# cryptostick-0v1.net
KiCad netlist of a schematic drawn in EAGLE
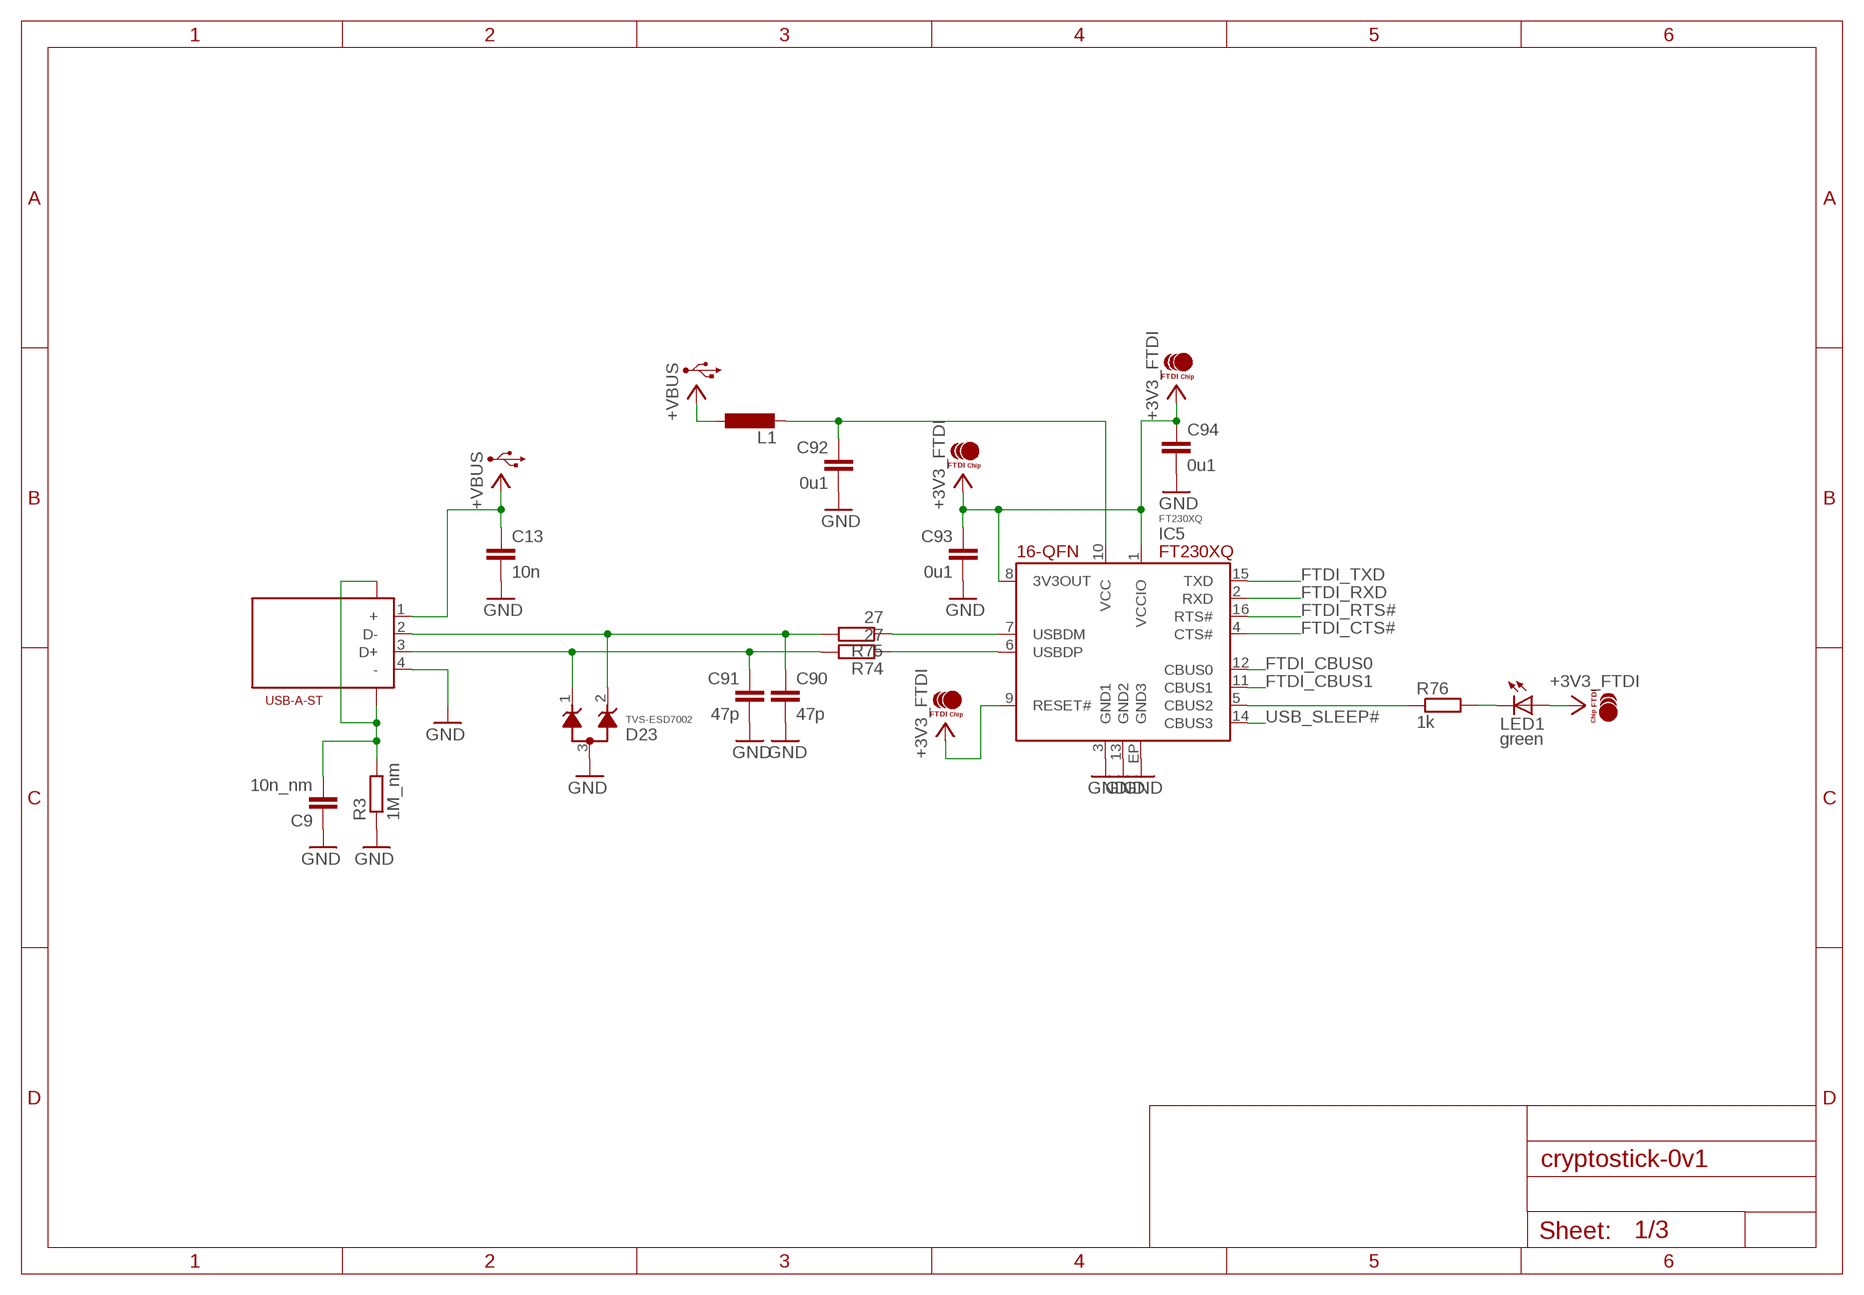
[diagram p0: schematic, sheet 1]
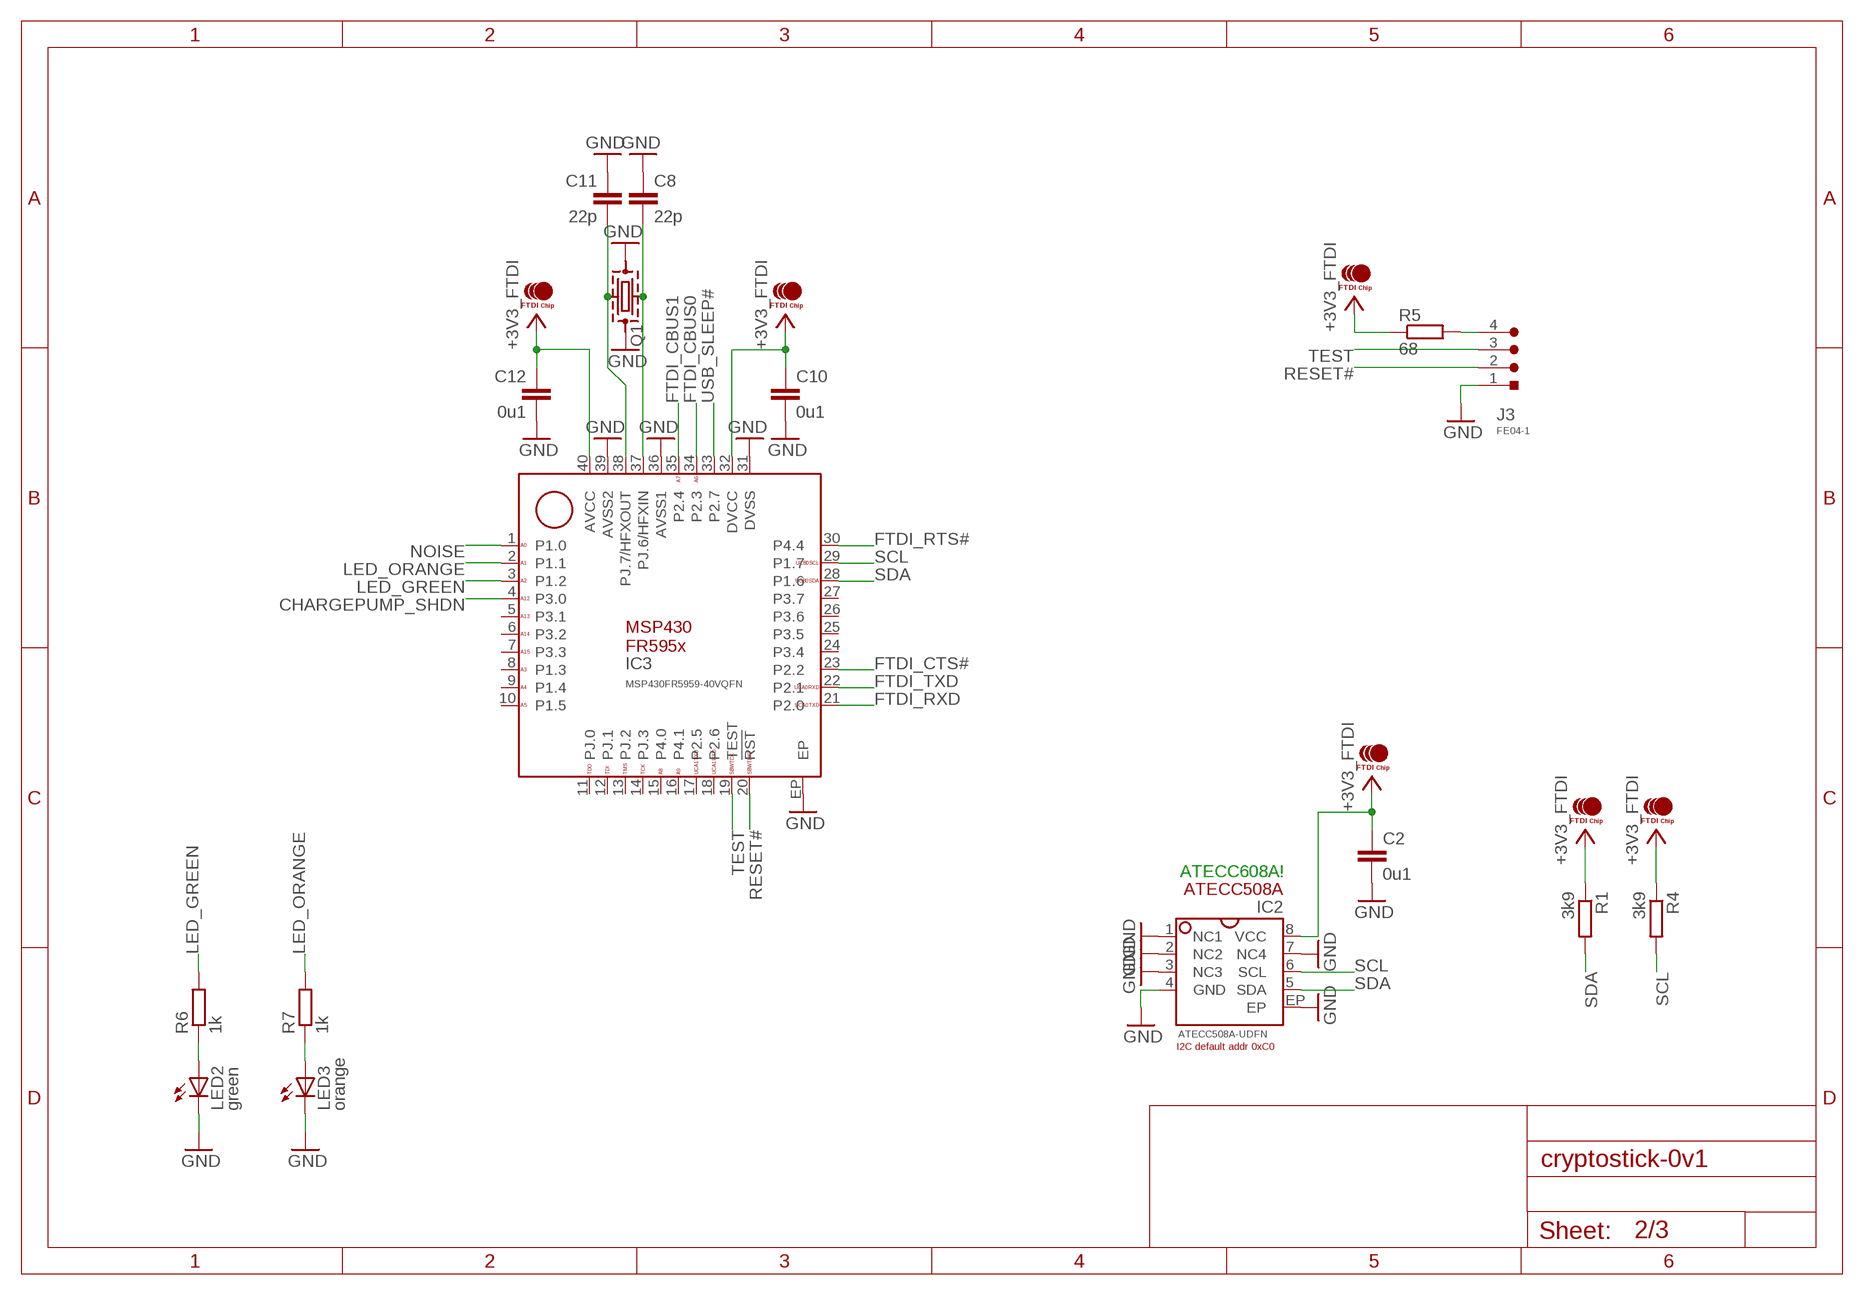
[diagram p1: schematic, sheet 2]
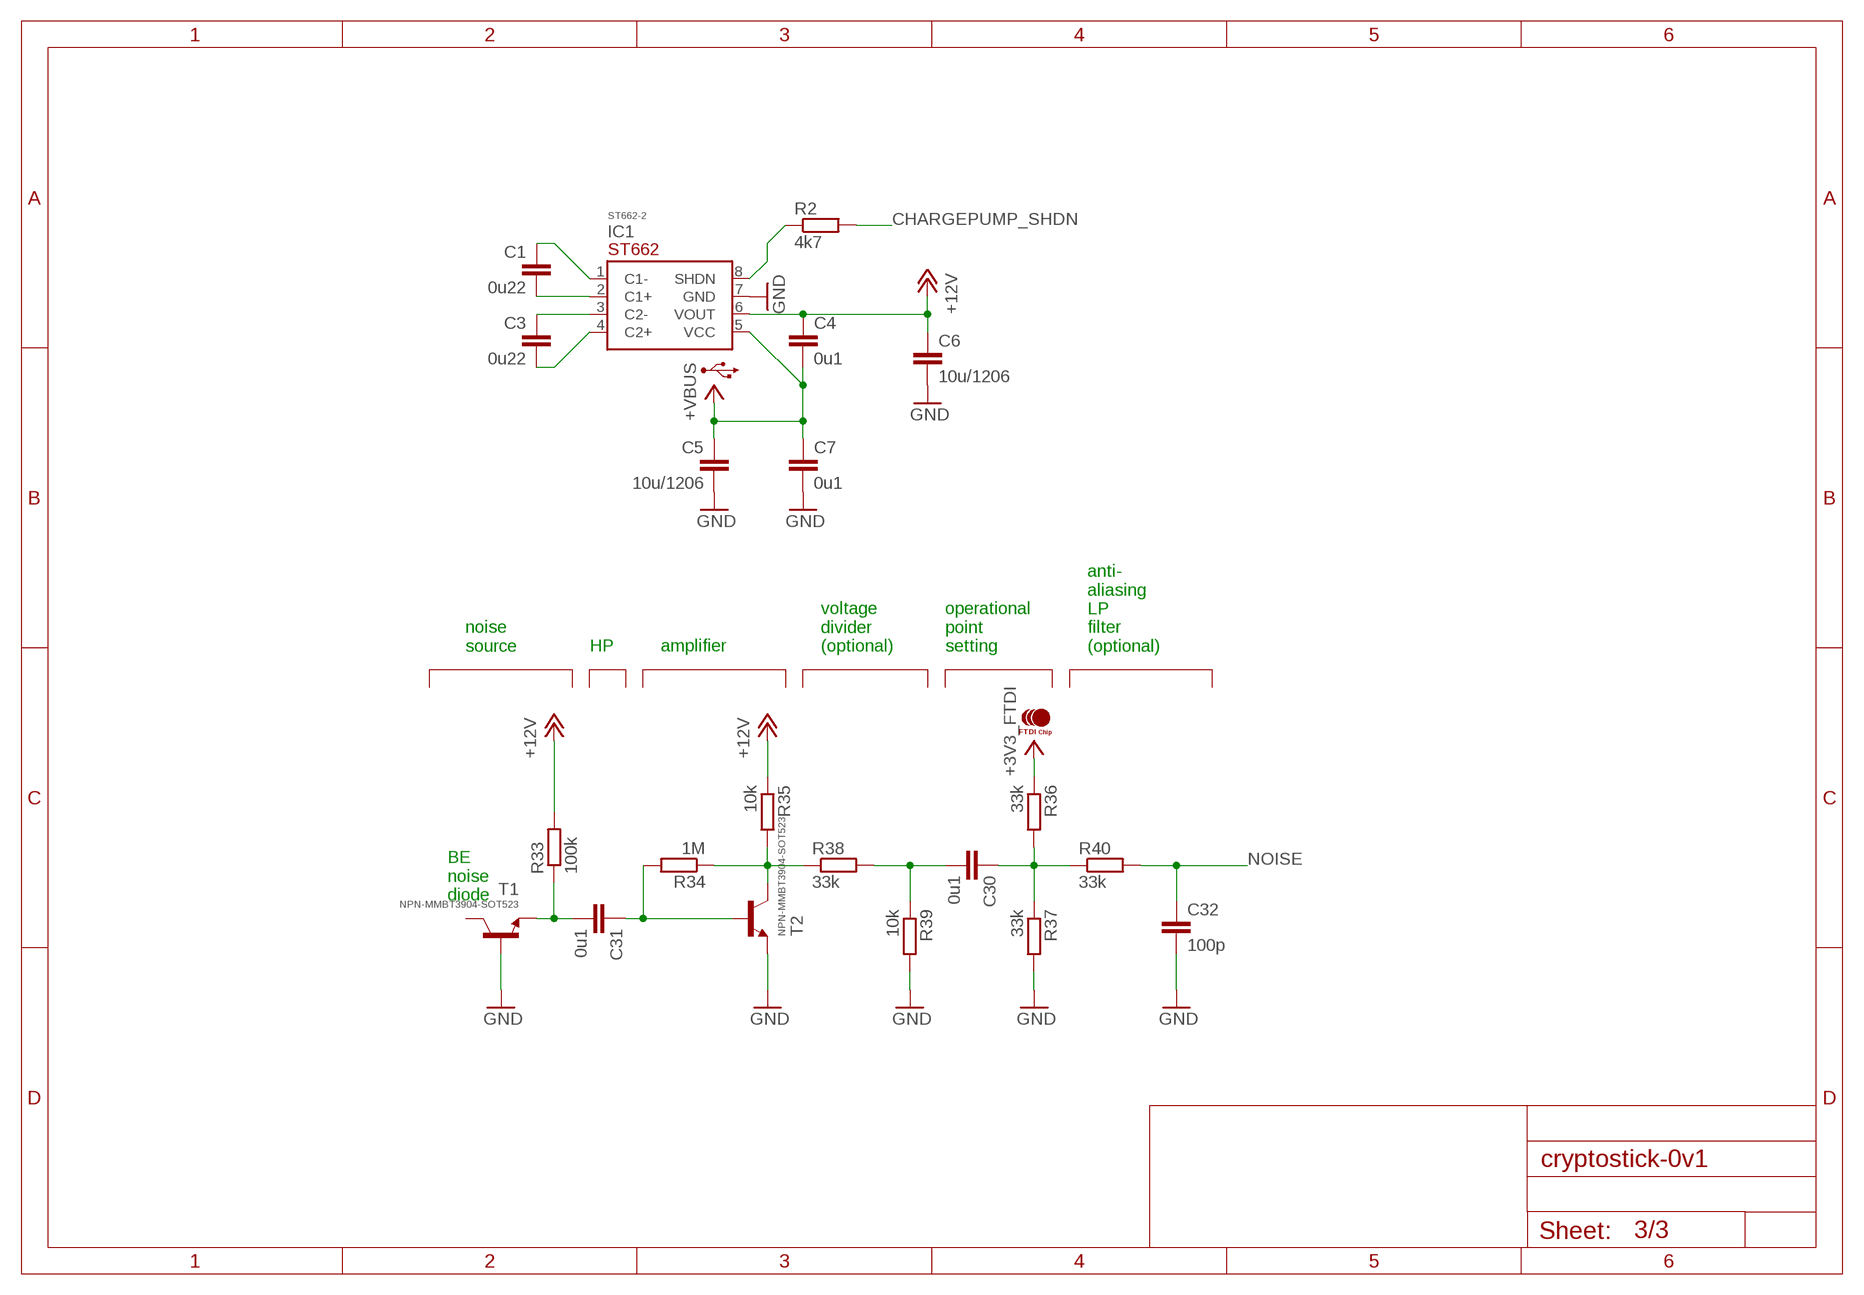
[diagram p2: schematic, sheet 3]

(export (version "E")
  (design (tool "Eeschema 10.0.6"))
  (components
    (comp (ref "C9")
      (value "10n_nm")
      (footprint "eagle-import:C0603")
      (libsource (lib "eagle-import") (part "C-EUC0603"))
    )
    (comp (ref "C13")
      (value "10n")
      (footprint "eagle-import:R0402-MCU")
      (libsource (lib "eagle-import") (part "C-EUR0402-MCU"))
    )
    (comp (ref "C90")
      (value "47p")
      (footprint "eagle-import:R0402-MCU")
      (libsource (lib "eagle-import") (part "C-EUR0402-MCU"))
    )
    (comp (ref "C91")
      (value "47p")
      (footprint "eagle-import:R0402-MCU")
      (libsource (lib "eagle-import") (part "C-EUR0402-MCU"))
    )
    (comp (ref "C92")
      (value "0u1")
      (footprint "eagle-import:R0402-MCU")
      (libsource (lib "eagle-import") (part "C-EUR0402-MCU"))
    )
    (comp (ref "C93")
      (value "0u1")
      (footprint "eagle-import:R0402-MCU")
      (libsource (lib "eagle-import") (part "C-EUR0402-MCU"))
    )
    (comp (ref "C94")
      (value "0u1")
      (footprint "eagle-import:R0402-MCU")
      (libsource (lib "eagle-import") (part "C-EUR0402-MCU"))
    )
    (comp (ref "D23")
      (value "TVS-ESD7002")
      (footprint "eagle-import:SC70-3")
      (libsource (lib "eagle-import") (part "TVS-ESD7002"))
    )
    (comp (ref "IC5")
      (value "FT230XQ")
      (footprint "eagle-import:16QFN-FT230X")
      (libsource (lib "eagle-import") (part "FT230XQ"))
    )
    (comp (ref "J1")
      (value "USB-A-ST")
      (footprint "eagle-import:USB-A-ST")
      (libsource (lib "eagle-import") (part "USB-A-ST"))
    )
    (comp (ref "L1")
      (value "L-EUR0402-MCU")
      (footprint "eagle-import:R0402-MCU")
      (libsource (lib "eagle-import") (part "L-EUR0402-MCU"))
    )
    (comp (ref "LED1")
      (value "green")
      (footprint "eagle-import:0603-SIDELED-RPI")
      (libsource (lib "eagle-import") (part "LED-0603-SIDELED-RPI"))
    )
    (comp (ref "R3")
      (value "1M_nm")
      (footprint "eagle-import:R0603")
      (libsource (lib "eagle-import") (part "R-EU_R0603"))
    )
    (comp (ref "R74")
      (value "27")
      (footprint "eagle-import:R0402-MCU")
      (libsource (lib "eagle-import") (part "R-EU_R0402-MCU"))
    )
    (comp (ref "R75")
      (value "27")
      (footprint "eagle-import:R0402-MCU")
      (libsource (lib "eagle-import") (part "R-EU_R0402-MCU"))
    )
    (comp (ref "R76")
      (value "1k")
      (footprint "eagle-import:R0402-MCU")
      (libsource (lib "eagle-import") (part "R-EU_R0402-MCU"))
    )
    (comp (ref "C2")
      (value "0u1")
      (footprint "eagle-import:R0402-MCU")
      (libsource (lib "eagle-import") (part "C-EUR0402-MCU"))
    )
    (comp (ref "C8")
      (value "22p")
      (footprint "eagle-import:R0402-MCU")
      (libsource (lib "eagle-import") (part "C-EUR0402-MCU"))
    )
    (comp (ref "C10")
      (value "0u1")
      (footprint "eagle-import:R0402-MCU")
      (libsource (lib "eagle-import") (part "C-EUR0402-MCU"))
    )
    (comp (ref "C11")
      (value "22p")
      (footprint "eagle-import:R0402-MCU")
      (libsource (lib "eagle-import") (part "C-EUR0402-MCU"))
    )
    (comp (ref "C12")
      (value "0u1")
      (footprint "eagle-import:R0402-MCU")
      (libsource (lib "eagle-import") (part "C-EUR0402-MCU"))
    )
    (comp (ref "IC2")
      (value "ATECC508A-UDFN")
      (footprint "eagle-import:8UDFN")
      (libsource (lib "eagle-import") (part "ATECC508A-UDFN"))
    )
    (comp (ref "IC3")
      (value "MSP430FR5959-40VQFN")
      (footprint "eagle-import:40VQFN-MSP430FR5959")
      (libsource (lib "eagle-import") (part "MSP430FR5959-40VQFN"))
    )
    (comp (ref "J3")
      (value "FE04-1")
      (footprint "eagle-import:FE04-1")
      (libsource (lib "eagle-import") (part "FE04-1"))
    )
    (comp (ref "LED2")
      (value "green")
      (footprint "eagle-import:0603-SIDELED-RPI")
      (libsource (lib "eagle-import") (part "LED-0603-SIDELED-RPI"))
    )
    (comp (ref "LED3")
      (value "orange")
      (footprint "eagle-import:0603-SIDELED-RPI")
      (libsource (lib "eagle-import") (part "LED-0603-SIDELED-RPI"))
    )
    (comp (ref "Q1")
      (value "XTAL-2.0X1.6")
      (footprint "eagle-import:XTAL-30MHZ-2.0X1.6")
      (libsource (lib "eagle-import") (part "XTAL-2.0X1.6"))
    )
    (comp (ref "R1")
      (value "3k9")
      (footprint "eagle-import:R0402-MCU")
      (libsource (lib "eagle-import") (part "R-EU_R0402-MCU"))
    )
    (comp (ref "R4")
      (value "3k9")
      (footprint "eagle-import:R0402-MCU")
      (libsource (lib "eagle-import") (part "R-EU_R0402-MCU"))
    )
    (comp (ref "R5")
      (value "68")
      (footprint "eagle-import:R0402-MCU")
      (libsource (lib "eagle-import") (part "R-EU_R0402-MCU"))
    )
    (comp (ref "R6")
      (value "1k")
      (footprint "eagle-import:R0402-MCU")
      (libsource (lib "eagle-import") (part "R-EU_R0402-MCU"))
    )
    (comp (ref "R7")
      (value "1k")
      (footprint "eagle-import:R0402-MCU")
      (libsource (lib "eagle-import") (part "R-EU_R0402-MCU"))
    )
    (comp (ref "C1")
      (value "0u22")
      (footprint "eagle-import:C0603")
      (libsource (lib "eagle-import") (part "C-EUC0603"))
    )
    (comp (ref "C3")
      (value "0u22")
      (footprint "eagle-import:C0603")
      (libsource (lib "eagle-import") (part "C-EUC0603"))
    )
    (comp (ref "C4")
      (value "0u1")
      (footprint "eagle-import:R0402-MCU")
      (libsource (lib "eagle-import") (part "C-EUR0402-MCU"))
    )
    (comp (ref "C5")
      (value "10u/1206")
      (footprint "eagle-import:C1206")
      (libsource (lib "eagle-import") (part "C-EUC1206"))
    )
    (comp (ref "C6")
      (value "10u/1206")
      (footprint "eagle-import:C1206")
      (libsource (lib "eagle-import") (part "C-EUC1206"))
    )
    (comp (ref "C7")
      (value "0u1")
      (footprint "eagle-import:R0402-MCU")
      (libsource (lib "eagle-import") (part "C-EUR0402-MCU"))
    )
    (comp (ref "C30")
      (value "0u1")
      (footprint "eagle-import:R0402-MCU")
      (libsource (lib "eagle-import") (part "C-EUR0402-MCU"))
    )
    (comp (ref "C31")
      (value "0u1")
      (footprint "eagle-import:R0402-MCU")
      (libsource (lib "eagle-import") (part "C-EUR0402-MCU"))
    )
    (comp (ref "C32")
      (value "100p")
      (footprint "eagle-import:R0402-MCU")
      (libsource (lib "eagle-import") (part "C-EUR0402-MCU"))
    )
    (comp (ref "IC1")
      (value "ST662-2")
      (footprint "eagle-import:8SOIC-2")
      (libsource (lib "eagle-import") (part "ST662-2"))
    )
    (comp (ref "R2")
      (value "4k7")
      (footprint "eagle-import:R0402-MCU")
      (libsource (lib "eagle-import") (part "R-EU_R0402-MCU"))
    )
    (comp (ref "R33")
      (value "100k")
      (footprint "eagle-import:R0402-MCU")
      (libsource (lib "eagle-import") (part "R-EU_R0402-MCU"))
    )
    (comp (ref "R34")
      (value "1M")
      (footprint "eagle-import:R0402-MCU")
      (libsource (lib "eagle-import") (part "R-EU_R0402-MCU"))
    )
    (comp (ref "R35")
      (value "10k")
      (footprint "eagle-import:R0402-MCU")
      (libsource (lib "eagle-import") (part "R-EU_R0402-MCU"))
    )
    (comp (ref "R36")
      (value "33k")
      (footprint "eagle-import:R0402-MCU")
      (libsource (lib "eagle-import") (part "R-EU_R0402-MCU"))
    )
    (comp (ref "R37")
      (value "33k")
      (footprint "eagle-import:R0402-MCU")
      (libsource (lib "eagle-import") (part "R-EU_R0402-MCU"))
    )
    (comp (ref "R38")
      (value "33k")
      (footprint "eagle-import:R0402-MCU")
      (libsource (lib "eagle-import") (part "R-EU_R0402-MCU"))
    )
    (comp (ref "R39")
      (value "10k")
      (footprint "eagle-import:R0402-MCU")
      (libsource (lib "eagle-import") (part "R-EU_R0402-MCU"))
    )
    (comp (ref "R40")
      (value "33k")
      (footprint "eagle-import:R0402-MCU")
      (libsource (lib "eagle-import") (part "R-EU_R0402-MCU"))
    )
    (comp (ref "T1")
      (value "NPN-MMBT3904-SOT523")
      (footprint "eagle-import:SOT523")
      (libsource (lib "eagle-import") (part "NPN-MMBT3904-SOT523"))
    )
    (comp (ref "T2")
      (value "NPN-MMBT3904-SOT523")
      (footprint "eagle-import:SOT523")
      (libsource (lib "eagle-import") (part "NPN-MMBT3904-SOT523"))
    )
  )
  (nets
    (net (code "1") (name "+3V3_FTDI") (class "Default")
      (node (ref "C10") (pin "1") (pinfunction "1_1") (pintype "passive"))
      (node (ref "C12") (pin "1") (pinfunction "1_1") (pintype "passive"))
      (node (ref "C2") (pin "1") (pinfunction "1_1") (pintype "passive"))
      (node (ref "C93") (pin "1") (pinfunction "1_1") (pintype "passive"))
      (node (ref "C94") (pin "1") (pinfunction "1_1") (pintype "passive"))
      (node (ref "IC2") (pin "8") (pinfunction "VCC_8") (pintype "bidirectional"))
      (node (ref "IC3") (pin "32") (pinfunction "DVCC_32") (pintype "power_in"))
      (node (ref "IC3") (pin "40") (pinfunction "AVCC_40") (pintype "power_in"))
      (node (ref "IC5") (pin "1") (pinfunction "VCCIO_1") (pintype "bidirectional"))
      (node (ref "IC5") (pin "8") (pinfunction "3V3OUT_8") (pintype "bidirectional"))
      (node (ref "IC5") (pin "9") (pinfunction "RESET#_9") (pintype "bidirectional"))
      (node (ref "LED1") (pin "A") (pinfunction "A_A") (pintype "passive"))
      (node (ref "R1") (pin "1") (pinfunction "1_1") (pintype "passive"))
      (node (ref "R36") (pin "1") (pinfunction "1_1") (pintype "passive"))
      (node (ref "R4") (pin "1") (pinfunction "1_1") (pintype "passive"))
      (node (ref "R5") (pin "1") (pinfunction "1_1") (pintype "passive"))
    )
    (net (code "2") (name "+12V") (class "Default")
      (node (ref "C4") (pin "1") (pinfunction "1_1") (pintype "passive"))
      (node (ref "C6") (pin "1") (pinfunction "1_1") (pintype "passive"))
      (node (ref "IC1") (pin "6") (pinfunction "VOUT_6") (pintype "bidirectional"))
      (node (ref "R33") (pin "2") (pinfunction "2_2") (pintype "passive"))
      (node (ref "R35") (pin "1") (pinfunction "1_1") (pintype "passive"))
    )
    (net (code "3") (name "+VBUS") (class "Default")
      (node (ref "C13") (pin "1") (pinfunction "1_1") (pintype "passive"))
      (node (ref "C4") (pin "2") (pinfunction "2_2") (pintype "passive"))
      (node (ref "C5") (pin "1") (pinfunction "1_1") (pintype "passive"))
      (node (ref "C7") (pin "1") (pinfunction "1_1") (pintype "passive"))
      (node (ref "IC1") (pin "5") (pinfunction "VCC_5") (pintype "bidirectional"))
      (node (ref "J1") (pin "1") (pinfunction "+_1") (pintype "bidirectional"))
      (node (ref "L1") (pin "1") (pinfunction "1_1") (pintype "passive"))
    )
    (net (code "4") (name "CHARGEPUMP_SHDN") (class "Default")
      (node (ref "IC3") (pin "4") (pinfunction "P3.0_4") (pintype "bidirectional"))
      (node (ref "R2") (pin "2") (pinfunction "2_2") (pintype "passive"))
    )
    (net (code "5") (name "FTDI_CBUS0") (class "Default")
      (node (ref "IC3") (pin "34") (pinfunction "P2.3_34") (pintype "bidirectional"))
      (node (ref "IC5") (pin "12") (pinfunction "CBUS0_12") (pintype "bidirectional"))
    )
    (net (code "6") (name "FTDI_CBUS1") (class "Default")
      (node (ref "IC3") (pin "35") (pinfunction "P2.4_35") (pintype "bidirectional"))
      (node (ref "IC5") (pin "11") (pinfunction "CBUS1_11") (pintype "bidirectional"))
    )
    (net (code "7") (name "FTDI_CTS#") (class "Default")
      (node (ref "IC3") (pin "23") (pinfunction "P2.2_23") (pintype "bidirectional"))
      (node (ref "IC5") (pin "4") (pinfunction "CTS#_4") (pintype "bidirectional"))
    )
    (net (code "8") (name "FTDI_RTS#") (class "Default")
      (node (ref "IC3") (pin "30") (pinfunction "P4.4_30") (pintype "bidirectional"))
      (node (ref "IC5") (pin "16") (pinfunction "RTS#_16") (pintype "bidirectional"))
    )
    (net (code "9") (name "FTDI_RXD") (class "Default")
      (node (ref "IC3") (pin "21") (pinfunction "P2.0_21") (pintype "bidirectional"))
      (node (ref "IC5") (pin "2") (pinfunction "RXD_2") (pintype "bidirectional"))
    )
    (net (code "10") (name "FTDI_TXD") (class "Default")
      (node (ref "IC3") (pin "22") (pinfunction "P2.1_22") (pintype "bidirectional"))
      (node (ref "IC5") (pin "15") (pinfunction "TXD_15") (pintype "bidirectional"))
    )
    (net (code "11") (name "GND") (class "Default")
      (node (ref "C10") (pin "2") (pinfunction "2_2") (pintype "passive"))
      (node (ref "C11") (pin "1") (pinfunction "1_1") (pintype "passive"))
      (node (ref "C12") (pin "2") (pinfunction "2_2") (pintype "passive"))
      (node (ref "C13") (pin "2") (pinfunction "2_2") (pintype "passive"))
      (node (ref "C2") (pin "2") (pinfunction "2_2") (pintype "passive"))
      (node (ref "C32") (pin "2") (pinfunction "2_2") (pintype "passive"))
      (node (ref "C5") (pin "2") (pinfunction "2_2") (pintype "passive"))
      (node (ref "C6") (pin "2") (pinfunction "2_2") (pintype "passive"))
      (node (ref "C7") (pin "2") (pinfunction "2_2") (pintype "passive"))
      (node (ref "C8") (pin "1") (pinfunction "1_1") (pintype "passive"))
      (node (ref "C9") (pin "1") (pinfunction "1_1") (pintype "passive"))
      (node (ref "C90") (pin "2") (pinfunction "2_2") (pintype "passive"))
      (node (ref "C91") (pin "2") (pinfunction "2_2") (pintype "passive"))
      (node (ref "C92") (pin "2") (pinfunction "2_2") (pintype "passive"))
      (node (ref "C93") (pin "2") (pinfunction "2_2") (pintype "passive"))
      (node (ref "C94") (pin "2") (pinfunction "2_2") (pintype "passive"))
      (node (ref "D23") (pin "3") (pinfunction "3_3") (pintype "bidirectional"))
      (node (ref "IC1") (pin "7") (pinfunction "GND_7") (pintype "bidirectional"))
      (node (ref "IC2") (pin "1") (pinfunction "NC1_1") (pintype "bidirectional"))
      (node (ref "IC2") (pin "2") (pinfunction "NC2_2") (pintype "bidirectional"))
      (node (ref "IC2") (pin "3") (pinfunction "NC3_3") (pintype "bidirectional"))
      (node (ref "IC2") (pin "4") (pinfunction "GND_4") (pintype "bidirectional"))
      (node (ref "IC2") (pin "7") (pinfunction "NC4_7") (pintype "bidirectional"))
      (node (ref "IC2") (pin "EP") (pinfunction "EP_EP") (pintype "bidirectional"))
      (node (ref "IC3") (pin "31") (pinfunction "DVSS_31") (pintype "power_in"))
      (node (ref "IC3") (pin "36") (pinfunction "AVSS1_36") (pintype "power_in"))
      (node (ref "IC3") (pin "39") (pinfunction "AVSS2_39") (pintype "power_in"))
      (node (ref "IC3") (pin "EP") (pinfunction "EP_EP") (pintype "bidirectional"))
      (node (ref "IC5") (pin "13") (pinfunction "GND2_13") (pintype "bidirectional"))
      (node (ref "IC5") (pin "3") (pinfunction "GND1_3") (pintype "bidirectional"))
      (node (ref "IC5") (pin "EP") (pinfunction "GND3_EP") (pintype "bidirectional"))
      (node (ref "J1") (pin "4") (pinfunction "-_4") (pintype "bidirectional"))
      (node (ref "J3") (pin "1") (pinfunction "1_1") (pintype "bidirectional"))
      (node (ref "LED2") (pin "C") (pinfunction "C_C") (pintype "passive"))
      (node (ref "LED3") (pin "C") (pinfunction "C_C") (pintype "passive"))
      (node (ref "Q1") (pin "2") (pinfunction "GND1_2") (pintype "bidirectional"))
      (node (ref "Q1") (pin "4") (pinfunction "GND2_4") (pintype "bidirectional"))
      (node (ref "R3") (pin "1") (pinfunction "1_1") (pintype "passive"))
      (node (ref "R37") (pin "2") (pinfunction "2_2") (pintype "passive"))
      (node (ref "R39") (pin "2") (pinfunction "2_2") (pintype "passive"))
      (node (ref "T1") (pin "1") (pinfunction "B_1") (pintype "passive"))
      (node (ref "T2") (pin "2") (pinfunction "E_2") (pintype "passive"))
    )
    (net (code "12") (name "LED_GREEN") (class "Default")
      (node (ref "IC3") (pin "3") (pinfunction "P1.2_3") (pintype "bidirectional"))
      (node (ref "R6") (pin "2") (pinfunction "2_2") (pintype "passive"))
    )
    (net (code "13") (name "LED_ORANGE") (class "Default")
      (node (ref "IC3") (pin "2") (pinfunction "P1.1_2") (pintype "bidirectional"))
      (node (ref "R7") (pin "2") (pinfunction "2_2") (pintype "passive"))
    )
    (net (code "14") (name "NOISE") (class "Default")
      (node (ref "C32") (pin "1") (pinfunction "1_1") (pintype "passive"))
      (node (ref "IC3") (pin "1") (pinfunction "P1.0_1") (pintype "bidirectional"))
      (node (ref "R40") (pin "2") (pinfunction "2_2") (pintype "passive"))
    )
    (net (code "15") (name "Net-(C9-Pad2)") (class "Default")
      (node (ref "C9") (pin "2") (pinfunction "2_2") (pintype "passive"))
      (node (ref "J1") (pin "SH1") (pinfunction "SH1_SH1") (pintype "bidirectional"))
      (node (ref "J1") (pin "SH2") (pinfunction "SH2_SH2") (pintype "bidirectional"))
      (node (ref "R3") (pin "2") (pinfunction "2_2") (pintype "passive"))
    )
    (net (code "16") (name "Net-(C30-Pad1)") (class "Default")
      (node (ref "C30") (pin "1") (pinfunction "1_1") (pintype "passive"))
      (node (ref "R36") (pin "2") (pinfunction "2_2") (pintype "passive"))
      (node (ref "R37") (pin "1") (pinfunction "1_1") (pintype "passive"))
      (node (ref "R40") (pin "1") (pinfunction "1_1") (pintype "passive"))
    )
    (net (code "17") (name "Net-(C30-Pad2)") (class "Default")
      (node (ref "C30") (pin "2") (pinfunction "2_2") (pintype "passive"))
      (node (ref "R38") (pin "2") (pinfunction "2_2") (pintype "passive"))
      (node (ref "R39") (pin "1") (pinfunction "1_1") (pintype "passive"))
    )
    (net (code "18") (name "Net-(IC1-C1+)") (class "Default")
      (node (ref "C1") (pin "2") (pinfunction "2_2") (pintype "passive"))
      (node (ref "IC1") (pin "2") (pinfunction "C1+_2") (pintype "bidirectional"))
    )
    (net (code "19") (name "Net-(IC1-C1-)") (class "Default")
      (node (ref "C1") (pin "1") (pinfunction "1_1") (pintype "passive"))
      (node (ref "IC1") (pin "1") (pinfunction "C1-_1") (pintype "bidirectional"))
    )
    (net (code "20") (name "Net-(IC1-C2+)") (class "Default")
      (node (ref "C3") (pin "2") (pinfunction "2_2") (pintype "passive"))
      (node (ref "IC1") (pin "4") (pinfunction "C2+_4") (pintype "bidirectional"))
    )
    (net (code "21") (name "Net-(IC1-C2-)") (class "Default")
      (node (ref "C3") (pin "1") (pinfunction "1_1") (pintype "passive"))
      (node (ref "IC1") (pin "3") (pinfunction "C2-_3") (pintype "bidirectional"))
    )
    (net (code "22") (name "Net-(IC1-SHDN)") (class "Default")
      (node (ref "IC1") (pin "8") (pinfunction "SHDN_8") (pintype "bidirectional"))
      (node (ref "R2") (pin "1") (pinfunction "1_1") (pintype "passive"))
    )
    (net (code "23") (name "Net-(IC3-PJ.6{slash}HFXIN)") (class "Default")
      (node (ref "C8") (pin "2") (pinfunction "2_2") (pintype "passive"))
      (node (ref "IC3") (pin "37") (pinfunction "PJ.6/HFXIN_37") (pintype "bidirectional"))
      (node (ref "Q1") (pin "3") (pinfunction "2_3") (pintype "bidirectional"))
    )
    (net (code "24") (name "Net-(IC3-PJ.7{slash}HFXOUT)") (class "Default")
      (node (ref "C11") (pin "2") (pinfunction "2_2") (pintype "passive"))
      (node (ref "IC3") (pin "38") (pinfunction "PJ.7/HFXOUT_38") (pintype "bidirectional"))
      (node (ref "Q1") (pin "1") (pinfunction "1_1") (pintype "bidirectional"))
    )
    (net (code "25") (name "Net-(IC5-CBUS2)") (class "Default")
      (node (ref "IC5") (pin "5") (pinfunction "CBUS2_5") (pintype "bidirectional"))
      (node (ref "R76") (pin "1") (pinfunction "1_1") (pintype "passive"))
    )
    (net (code "26") (name "Net-(IC5-USBDM)") (class "Default")
      (node (ref "IC5") (pin "7") (pinfunction "USBDM_7") (pintype "bidirectional"))
      (node (ref "R75") (pin "1") (pinfunction "1_1") (pintype "passive"))
    )
    (net (code "27") (name "Net-(IC5-USBDP)") (class "Default")
      (node (ref "IC5") (pin "6") (pinfunction "USBDP_6") (pintype "bidirectional"))
      (node (ref "R74") (pin "1") (pinfunction "1_1") (pintype "passive"))
    )
    (net (code "28") (name "Net-(IC5-VCC)") (class "Default")
      (node (ref "C92") (pin "1") (pinfunction "1_1") (pintype "passive"))
      (node (ref "IC5") (pin "10") (pinfunction "VCC_10") (pintype "bidirectional"))
      (node (ref "L1") (pin "2") (pinfunction "2_2") (pintype "passive"))
    )
    (net (code "29") (name "Net-(J1-D+)") (class "Default")
      (node (ref "C91") (pin "1") (pinfunction "1_1") (pintype "passive"))
      (node (ref "D23") (pin "1") (pinfunction "1_1") (pintype "bidirectional"))
      (node (ref "J1") (pin "3") (pinfunction "D+_3") (pintype "bidirectional"))
      (node (ref "R74") (pin "2") (pinfunction "2_2") (pintype "passive"))
    )
    (net (code "30") (name "Net-(J1-D-)") (class "Default")
      (node (ref "C90") (pin "1") (pinfunction "1_1") (pintype "passive"))
      (node (ref "D23") (pin "2") (pinfunction "2_2") (pintype "bidirectional"))
      (node (ref "J1") (pin "2") (pinfunction "D-_2") (pintype "bidirectional"))
      (node (ref "R75") (pin "2") (pinfunction "2_2") (pintype "passive"))
    )
    (net (code "31") (name "Net-(J3-Pad4)") (class "Default")
      (node (ref "J3") (pin "4") (pinfunction "4_4") (pintype "bidirectional"))
      (node (ref "R5") (pin "2") (pinfunction "2_2") (pintype "passive"))
    )
    (net (code "32") (name "Net-(LED1-PadC)") (class "Default")
      (node (ref "LED1") (pin "C") (pinfunction "C_C") (pintype "passive"))
      (node (ref "R76") (pin "2") (pinfunction "2_2") (pintype "passive"))
    )
    (net (code "33") (name "Net-(LED2-PadA)") (class "Default")
      (node (ref "LED2") (pin "A") (pinfunction "A_A") (pintype "passive"))
      (node (ref "R6") (pin "1") (pinfunction "1_1") (pintype "passive"))
    )
    (net (code "34") (name "Net-(LED3-PadA)") (class "Default")
      (node (ref "LED3") (pin "A") (pinfunction "A_A") (pintype "passive"))
      (node (ref "R7") (pin "1") (pinfunction "1_1") (pintype "passive"))
    )
    (net (code "35") (name "Net-(T1-E)") (class "Default")
      (node (ref "C31") (pin "2") (pinfunction "2_2") (pintype "passive"))
      (node (ref "R33") (pin "1") (pinfunction "1_1") (pintype "passive"))
      (node (ref "T1") (pin "2") (pinfunction "E_2") (pintype "passive"))
    )
    (net (code "36") (name "Net-(T2-B)") (class "Default")
      (node (ref "C31") (pin "1") (pinfunction "1_1") (pintype "passive"))
      (node (ref "R34") (pin "2") (pinfunction "2_2") (pintype "passive"))
      (node (ref "T2") (pin "1") (pinfunction "B_1") (pintype "passive"))
    )
    (net (code "37") (name "Net-(T2-C)") (class "Default")
      (node (ref "R34") (pin "1") (pinfunction "1_1") (pintype "passive"))
      (node (ref "R35") (pin "2") (pinfunction "2_2") (pintype "passive"))
      (node (ref "R38") (pin "1") (pinfunction "1_1") (pintype "passive"))
      (node (ref "T2") (pin "3") (pinfunction "C_3") (pintype "passive"))
    )
    (net (code "38") (name "RESET#") (class "Default")
      (node (ref "IC3") (pin "20") (pinfunction "~{RST}_20") (pintype "bidirectional"))
      (node (ref "J3") (pin "2") (pinfunction "2_2") (pintype "bidirectional"))
    )
    (net (code "39") (name "SCL") (class "Default")
      (node (ref "IC2") (pin "6") (pinfunction "SCL_6") (pintype "bidirectional"))
      (node (ref "IC3") (pin "29") (pinfunction "P1.7_29") (pintype "bidirectional"))
      (node (ref "R4") (pin "2") (pinfunction "2_2") (pintype "passive"))
    )
    (net (code "40") (name "SDA") (class "Default")
      (node (ref "IC2") (pin "5") (pinfunction "SDA_5") (pintype "bidirectional"))
      (node (ref "IC3") (pin "28") (pinfunction "P1.6_28") (pintype "bidirectional"))
      (node (ref "R1") (pin "2") (pinfunction "2_2") (pintype "passive"))
    )
    (net (code "41") (name "TEST") (class "Default")
      (node (ref "IC3") (pin "19") (pinfunction "TEST_19") (pintype "bidirectional"))
      (node (ref "J3") (pin "3") (pinfunction "3_3") (pintype "bidirectional"))
    )
    (net (code "42") (name "USB_SLEEP#") (class "Default")
      (node (ref "IC3") (pin "33") (pinfunction "P2.7_33") (pintype "bidirectional"))
      (node (ref "IC5") (pin "14") (pinfunction "CBUS3_14") (pintype "bidirectional"))
    )
    (net (code "43") (name "unconnected-(IC3-P1.3-Pad8)") (class "Default")
      (node (ref "IC3") (pin "8") (pinfunction "P1.3_8") (pintype "bidirectional"))
    )
    (net (code "44") (name "unconnected-(IC3-P1.4-Pad9)") (class "Default")
      (node (ref "IC3") (pin "9") (pinfunction "P1.4_9") (pintype "bidirectional"))
    )
    (net (code "45") (name "unconnected-(IC3-P1.5-Pad10)") (class "Default")
      (node (ref "IC3") (pin "10") (pinfunction "P1.5_10") (pintype "bidirectional"))
    )
    (net (code "46") (name "unconnected-(IC3-P2.5-Pad17)") (class "Default")
      (node (ref "IC3") (pin "17") (pinfunction "P2.5_17") (pintype "bidirectional"))
    )
    (net (code "47") (name "unconnected-(IC3-P2.6-Pad18)") (class "Default")
      (node (ref "IC3") (pin "18") (pinfunction "P2.6_18") (pintype "bidirectional"))
    )
    (net (code "48") (name "unconnected-(IC3-P3.1-Pad5)") (class "Default")
      (node (ref "IC3") (pin "5") (pinfunction "P3.1_5") (pintype "bidirectional"))
    )
    (net (code "49") (name "unconnected-(IC3-P3.2-Pad6)") (class "Default")
      (node (ref "IC3") (pin "6") (pinfunction "P3.2_6") (pintype "bidirectional"))
    )
    (net (code "50") (name "unconnected-(IC3-P3.3-Pad7)") (class "Default")
      (node (ref "IC3") (pin "7") (pinfunction "P3.3_7") (pintype "bidirectional"))
    )
    (net (code "51") (name "unconnected-(IC3-P3.4-Pad24)") (class "Default")
      (node (ref "IC3") (pin "24") (pinfunction "P3.4_24") (pintype "bidirectional"))
    )
    (net (code "52") (name "unconnected-(IC3-P3.5-Pad25)") (class "Default")
      (node (ref "IC3") (pin "25") (pinfunction "P3.5_25") (pintype "bidirectional"))
    )
    (net (code "53") (name "unconnected-(IC3-P3.6-Pad26)") (class "Default")
      (node (ref "IC3") (pin "26") (pinfunction "P3.6_26") (pintype "bidirectional"))
    )
    (net (code "54") (name "unconnected-(IC3-P3.7-Pad27)") (class "Default")
      (node (ref "IC3") (pin "27") (pinfunction "P3.7_27") (pintype "bidirectional"))
    )
    (net (code "55") (name "unconnected-(IC3-P4.0-Pad15)") (class "Default")
      (node (ref "IC3") (pin "15") (pinfunction "P4.0_15") (pintype "bidirectional"))
    )
    (net (code "56") (name "unconnected-(IC3-P4.1-Pad16)") (class "Default")
      (node (ref "IC3") (pin "16") (pinfunction "P4.1_16") (pintype "bidirectional"))
    )
    (net (code "57") (name "unconnected-(IC3-PJ.0-Pad11)") (class "Default")
      (node (ref "IC3") (pin "11") (pinfunction "PJ.0_11") (pintype "bidirectional"))
    )
    (net (code "58") (name "unconnected-(IC3-PJ.1-Pad12)") (class "Default")
      (node (ref "IC3") (pin "12") (pinfunction "PJ.1_12") (pintype "bidirectional"))
    )
    (net (code "59") (name "unconnected-(IC3-PJ.2-Pad13)") (class "Default")
      (node (ref "IC3") (pin "13") (pinfunction "PJ.2_13") (pintype "bidirectional"))
    )
    (net (code "60") (name "unconnected-(IC3-PJ.3-Pad14)") (class "Default")
      (node (ref "IC3") (pin "14") (pinfunction "PJ.3_14") (pintype "bidirectional"))
    )
    (net (code "61") (name "unconnected-(T1-C-Pad3)") (class "Default")
      (node (ref "T1") (pin "3") (pinfunction "C_3") (pintype "passive"))
    )
  )
)
